# tinyduino-breakout-mk-5_0.net
KiCad netlist of a schematic drawn in EAGLE
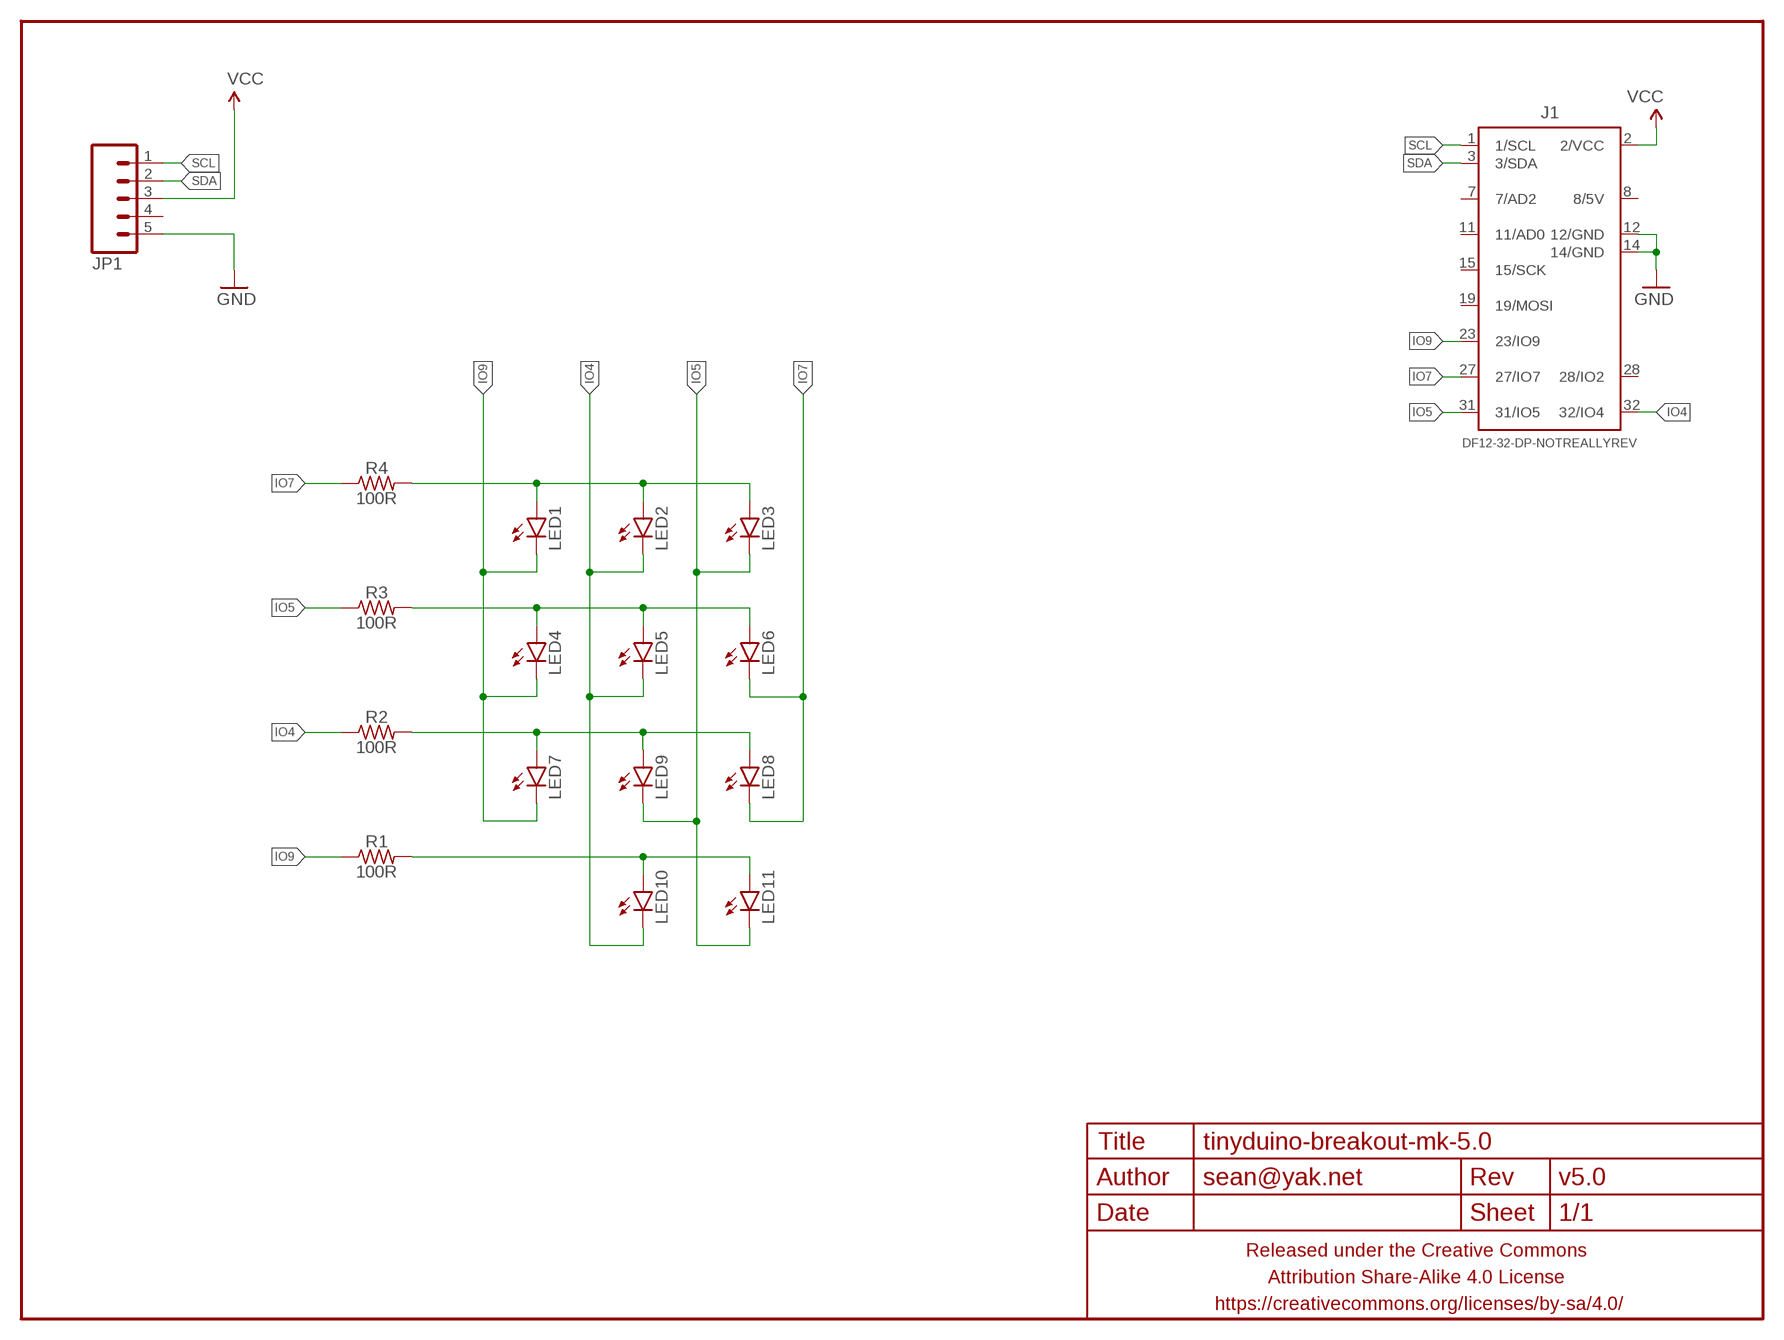
[diagram p0: schematic, sheet 1]

(export (version "E")
  (design (tool "Eeschema 10.0.6"))
  (components
    (comp (ref "FRAME1")
      (value "FRAME-LETTERNO_PACKAGE")
      (footprint "eagle-import:DUMMY")
      (fields (field (name "DESIGNER") "sean@yak.net") (field (name "VERSION") "v5.0"))
      (libsource (lib "eagle-import") (part "FRAME-LETTERNO_PACKAGE"))
    )
    (comp (ref "J1")
      (value "DF12-32-DP-NOTREALLYREV")
      (footprint "eagle-import:DF12-32-DP-I2C+EXTRA-REV")
      (libsource (lib "eagle-import") (part "DF12-32-DP-NOTREALLYREV"))
    )
    (comp (ref "JP1")
      (value "M05SMD-SHORT")
      (footprint "eagle-import:1X05-SMD-SHORT")
      (libsource (lib "eagle-import") (part "M05SMD-SHORT"))
    )
    (comp (ref "LED1")
      (value "LED0603")
      (footprint "eagle-import:LED-0603")
      (libsource (lib "eagle-import") (part "LED0603"))
    )
    (comp (ref "LED2")
      (value "LED0603")
      (footprint "eagle-import:LED-0603")
      (libsource (lib "eagle-import") (part "LED0603"))
    )
    (comp (ref "LED3")
      (value "LED0603")
      (footprint "eagle-import:LED-0603")
      (libsource (lib "eagle-import") (part "LED0603"))
    )
    (comp (ref "LED4")
      (value "LED0603")
      (footprint "eagle-import:LED-0603")
      (libsource (lib "eagle-import") (part "LED0603"))
    )
    (comp (ref "LED5")
      (value "LED0603")
      (footprint "eagle-import:LED-0603")
      (libsource (lib "eagle-import") (part "LED0603"))
    )
    (comp (ref "LED6")
      (value "LED0603")
      (footprint "eagle-import:LED-0603")
      (libsource (lib "eagle-import") (part "LED0603"))
    )
    (comp (ref "LED7")
      (value "LED0603")
      (footprint "eagle-import:LED-0603")
      (libsource (lib "eagle-import") (part "LED0603"))
    )
    (comp (ref "LED8")
      (value "LED0603")
      (footprint "eagle-import:LED-0603")
      (libsource (lib "eagle-import") (part "LED0603"))
    )
    (comp (ref "LED9")
      (value "LED0603")
      (footprint "eagle-import:LED-0603")
      (libsource (lib "eagle-import") (part "LED0603"))
    )
    (comp (ref "LED10")
      (value "LED0603")
      (footprint "eagle-import:LED-0603")
      (libsource (lib "eagle-import") (part "LED0603"))
    )
    (comp (ref "LED11")
      (value "LED0603")
      (footprint "eagle-import:LED-0603")
      (libsource (lib "eagle-import") (part "LED0603"))
    )
    (comp (ref "R1")
      (value "100R")
      (footprint "eagle-import:R0603")
      (libsource (lib "eagle-import") (part "RESISTORR0603"))
    )
    (comp (ref "R2")
      (value "100R")
      (footprint "eagle-import:R0603")
      (libsource (lib "eagle-import") (part "RESISTORR0603"))
    )
    (comp (ref "R3")
      (value "100R")
      (footprint "eagle-import:R0603")
      (libsource (lib "eagle-import") (part "RESISTORR0603"))
    )
    (comp (ref "R4")
      (value "100R")
      (footprint "eagle-import:R0603")
      (libsource (lib "eagle-import") (part "RESISTORR0603"))
    )
  )
  (nets
    (net (code "1") (name "GND") (class "Default")
      (node (ref "J1") (pin "12") (pinfunction "12/GND_12") (pintype "bidirectional"))
      (node (ref "J1") (pin "14") (pinfunction "14/GND_14") (pintype "bidirectional"))
      (node (ref "JP1") (pin "5") (pinfunction "5_5") (pintype "passive"))
    )
    (net (code "2") (name "IO4") (class "Default")
      (node (ref "J1") (pin "32") (pinfunction "32/IO4_32") (pintype "bidirectional"))
      (node (ref "LED10") (pin "C") (pinfunction "C_C") (pintype "passive"))
      (node (ref "LED2") (pin "C") (pinfunction "C_C") (pintype "passive"))
      (node (ref "LED5") (pin "C") (pinfunction "C_C") (pintype "passive"))
      (node (ref "R2") (pin "1") (pinfunction "1_1") (pintype "passive"))
    )
    (net (code "3") (name "IO5") (class "Default")
      (node (ref "J1") (pin "31") (pinfunction "31/IO5_31") (pintype "bidirectional"))
      (node (ref "LED11") (pin "C") (pinfunction "C_C") (pintype "passive"))
      (node (ref "LED3") (pin "C") (pinfunction "C_C") (pintype "passive"))
      (node (ref "LED9") (pin "C") (pinfunction "C_C") (pintype "passive"))
      (node (ref "R3") (pin "1") (pinfunction "1_1") (pintype "passive"))
    )
    (net (code "4") (name "IO7") (class "Default")
      (node (ref "J1") (pin "27") (pinfunction "27/IO7_27") (pintype "bidirectional"))
      (node (ref "LED6") (pin "C") (pinfunction "C_C") (pintype "passive"))
      (node (ref "LED8") (pin "C") (pinfunction "C_C") (pintype "passive"))
      (node (ref "R4") (pin "1") (pinfunction "1_1") (pintype "passive"))
    )
    (net (code "5") (name "IO9") (class "Default")
      (node (ref "J1") (pin "23") (pinfunction "23/IO9_23") (pintype "bidirectional"))
      (node (ref "LED1") (pin "C") (pinfunction "C_C") (pintype "passive"))
      (node (ref "LED4") (pin "C") (pinfunction "C_C") (pintype "passive"))
      (node (ref "LED7") (pin "C") (pinfunction "C_C") (pintype "passive"))
      (node (ref "R1") (pin "1") (pinfunction "1_1") (pintype "passive"))
    )
    (net (code "6") (name "Net-(LED1-PadA)") (class "Default")
      (node (ref "LED1") (pin "A") (pinfunction "A_A") (pintype "passive"))
      (node (ref "LED2") (pin "A") (pinfunction "A_A") (pintype "passive"))
      (node (ref "LED3") (pin "A") (pinfunction "A_A") (pintype "passive"))
      (node (ref "R4") (pin "2") (pinfunction "2_2") (pintype "passive"))
    )
    (net (code "7") (name "Net-(LED4-PadA)") (class "Default")
      (node (ref "LED4") (pin "A") (pinfunction "A_A") (pintype "passive"))
      (node (ref "LED5") (pin "A") (pinfunction "A_A") (pintype "passive"))
      (node (ref "LED6") (pin "A") (pinfunction "A_A") (pintype "passive"))
      (node (ref "R3") (pin "2") (pinfunction "2_2") (pintype "passive"))
    )
    (net (code "8") (name "Net-(LED7-PadA)") (class "Default")
      (node (ref "LED7") (pin "A") (pinfunction "A_A") (pintype "passive"))
      (node (ref "LED8") (pin "A") (pinfunction "A_A") (pintype "passive"))
      (node (ref "LED9") (pin "A") (pinfunction "A_A") (pintype "passive"))
      (node (ref "R2") (pin "2") (pinfunction "2_2") (pintype "passive"))
    )
    (net (code "9") (name "Net-(LED10-PadA)") (class "Default")
      (node (ref "LED10") (pin "A") (pinfunction "A_A") (pintype "passive"))
      (node (ref "LED11") (pin "A") (pinfunction "A_A") (pintype "passive"))
      (node (ref "R1") (pin "2") (pinfunction "2_2") (pintype "passive"))
    )
    (net (code "10") (name "SCL") (class "Default")
      (node (ref "J1") (pin "1") (pinfunction "1/SCL_1") (pintype "bidirectional"))
      (node (ref "JP1") (pin "1") (pinfunction "1_1") (pintype "passive"))
    )
    (net (code "11") (name "SDA") (class "Default")
      (node (ref "J1") (pin "3") (pinfunction "3/SDA_3") (pintype "bidirectional"))
      (node (ref "JP1") (pin "2") (pinfunction "2_2") (pintype "passive"))
    )
    (net (code "12") (name "VCC") (class "Default")
      (node (ref "J1") (pin "2") (pinfunction "2/VCC_2") (pintype "bidirectional"))
      (node (ref "JP1") (pin "3") (pinfunction "3_3") (pintype "passive"))
    )
    (net (code "13") (name "unconnected-(J1-7{slash}AD2-Pad7)") (class "Default")
      (node (ref "J1") (pin "7") (pinfunction "7/AD2_7") (pintype "bidirectional"))
    )
    (net (code "14") (name "unconnected-(J1-8{slash}5V-Pad8)") (class "Default")
      (node (ref "J1") (pin "8") (pinfunction "8/5V_8") (pintype "bidirectional"))
    )
    (net (code "15") (name "unconnected-(J1-11{slash}AD0-Pad11)") (class "Default")
      (node (ref "J1") (pin "11") (pinfunction "11/AD0_11") (pintype "bidirectional"))
    )
    (net (code "16") (name "unconnected-(J1-15{slash}SCK-Pad15)") (class "Default")
      (node (ref "J1") (pin "15") (pinfunction "15/SCK_15") (pintype "bidirectional"))
    )
    (net (code "17") (name "unconnected-(J1-19{slash}MOSI-Pad19)") (class "Default")
      (node (ref "J1") (pin "19") (pinfunction "19/MOSI_19") (pintype "bidirectional"))
    )
    (net (code "18") (name "unconnected-(J1-28{slash}IO2-Pad28)") (class "Default")
      (node (ref "J1") (pin "28") (pinfunction "28/IO2_28") (pintype "bidirectional"))
    )
    (net (code "19") (name "unconnected-(JP1-Pad4)") (class "Default")
      (node (ref "JP1") (pin "4") (pinfunction "4_4") (pintype "passive"))
    )
  )
)
